# psu.net
KiCad netlist of a schematic drawn in EAGLE
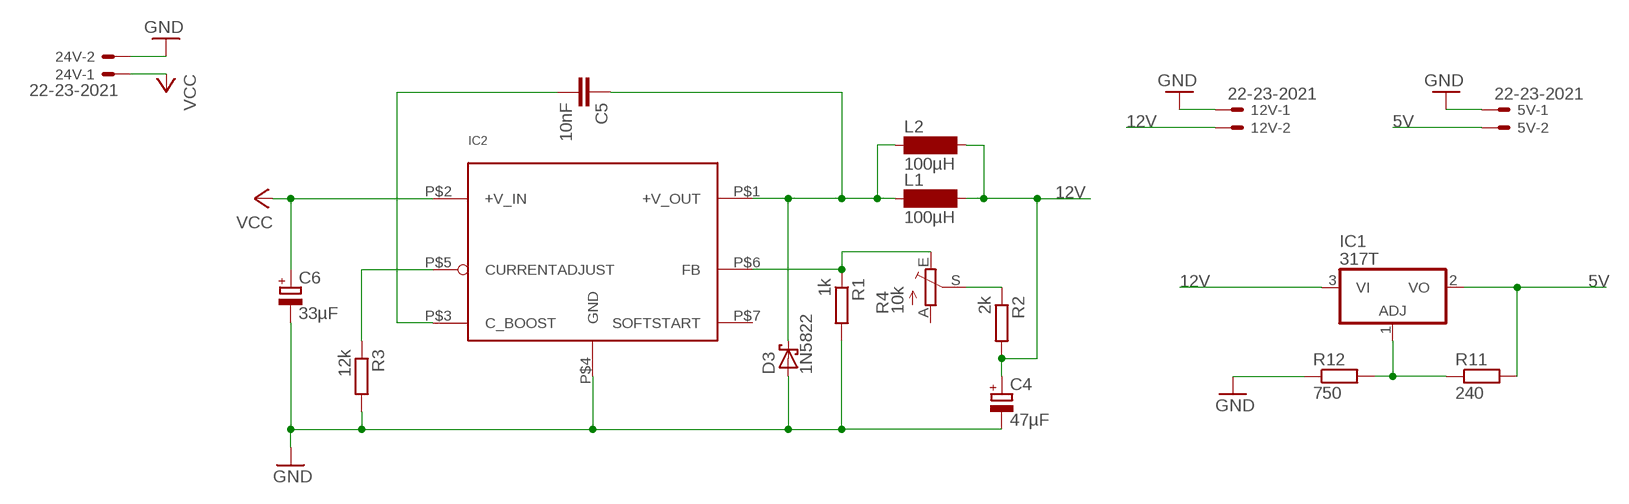
[diagram p0: schematic, sheet 1]

(export (version "E")
  (design (tool "Eeschema 10.0.6"))
  (components
    (comp (ref "5V")
      (value "22-23-2021")
      (footprint "eagle-import:22-23-2021")
      (fields (field (name "MF") "MOLEX"))
      (libsource (lib "eagle-import") (part "22-23-2021"))
    )
    (comp (ref "12V")
      (value "22-23-2021")
      (footprint "eagle-import:22-23-2021")
      (fields (field (name "MF") "MOLEX"))
      (libsource (lib "eagle-import") (part "22-23-2021"))
    )
    (comp (ref "24V")
      (value "22-23-2021")
      (footprint "eagle-import:22-23-2021")
      (fields (field (name "MF") "MOLEX"))
      (libsource (lib "eagle-import") (part "22-23-2021"))
    )
    (comp (ref "C4")
      (value "47µF")
      (footprint "eagle-import:E2,5-5")
      (libsource (lib "eagle-import") (part "CPOL-EUE2.5-5"))
    )
    (comp (ref "C5")
      (value "10nF")
      (footprint "eagle-import:C5B2.5")
      (libsource (lib "eagle-import") (part "C5/2.5"))
    )
    (comp (ref "C6")
      (value "33µF")
      (footprint "eagle-import:E2,5-5")
      (libsource (lib "eagle-import") (part "CPOL-EUE2.5-5"))
    )
    (comp (ref "D3")
      (value "1N5822")
      (footprint "eagle-import:C4111-15")
      (libsource (lib "eagle-import") (part "1N5908"))
    )
    (comp (ref "IC1")
      (value "317T")
      (footprint "eagle-import:TO220H")
      (libsource (lib "eagle-import") (part "317T"))
    )
    (comp (ref "IC2")
      (value "LM2576-T05D")
      (footprint "eagle-import:TO220-5_STAGGERED")
      (libsource (lib "eagle-import") (part "LM2576-T05D"))
    )
    (comp (ref "L1")
      (value "100µH")
      (footprint "eagle-import:SD75")
      (libsource (lib "eagle-import") (part "SD75"))
    )
    (comp (ref "L2")
      (value "100µH")
      (footprint "eagle-import:SD75")
      (libsource (lib "eagle-import") (part "SD75"))
    )
    (comp (ref "R1")
      (value "1k")
      (footprint "eagle-import:0207_10")
      (libsource (lib "eagle-import") (part "R-EU_0207/10"))
    )
    (comp (ref "R2")
      (value "2k")
      (footprint "eagle-import:0207_10")
      (libsource (lib "eagle-import") (part "R-EU_0207/10"))
    )
    (comp (ref "R3")
      (value "12k")
      (footprint "eagle-import:0207_10")
      (libsource (lib "eagle-import") (part "R-EU_0207/10"))
    )
    (comp (ref "R4")
      (value "10k")
      (footprint "eagle-import:B25P")
      (libsource (lib "eagle-import") (part "TRIM_EU-B25P"))
    )
    (comp (ref "R11")
      (value "240")
      (footprint "eagle-import:0207_10")
      (libsource (lib "eagle-import") (part "R-EU_0207/10"))
    )
    (comp (ref "R12")
      (value "750")
      (footprint "eagle-import:0207_10")
      (libsource (lib "eagle-import") (part "R-EU_0207/10"))
    )
  )
  (nets
    (net (code "1") (name "/5V") (class "Default")
      (node (ref "5V") (pin "2") (pinfunction "S_2") (pintype "passive"))
      (node (ref "IC1") (pin "2") (pinfunction "VO_2") (pintype "passive"))
      (node (ref "R11") (pin "2") (pinfunction "2_2") (pintype "passive"))
    )
    (net (code "2") (name "/12V") (class "Default")
      (node (ref "12V") (pin "2") (pinfunction "S_2") (pintype "passive"))
      (node (ref "C4") (pin "+") (pinfunction "+_+") (pintype "passive"))
      (node (ref "IC1") (pin "3") (pinfunction "VI_3") (pintype "input"))
      (node (ref "L1") (pin "2") (pinfunction "2_2") (pintype "passive"))
      (node (ref "L2") (pin "2") (pinfunction "2_2") (pintype "passive"))
      (node (ref "R2") (pin "2") (pinfunction "2_2") (pintype "passive"))
    )
    (net (code "3") (name "GND") (class "Default")
      (node (ref "12V") (pin "1") (pinfunction "S_1") (pintype "passive"))
      (node (ref "24V") (pin "2") (pinfunction "S_2") (pintype "passive"))
      (node (ref "5V") (pin "1") (pinfunction "S_1") (pintype "passive"))
      (node (ref "C4") (pin "-") (pinfunction "-_-") (pintype "passive"))
      (node (ref "C6") (pin "-") (pinfunction "-_-") (pintype "passive"))
      (node (ref "D3") (pin "A") (pinfunction "A_A") (pintype "passive"))
      (node (ref "IC2") (pin "P$4") (pinfunction "GND_P$4") (pintype "power_in"))
      (node (ref "R1") (pin "2") (pinfunction "2_2") (pintype "passive"))
      (node (ref "R12") (pin "1") (pinfunction "1_1") (pintype "passive"))
      (node (ref "R3") (pin "2") (pinfunction "2_2") (pintype "passive"))
    )
    (net (code "4") (name "Net-(IC1-ADJ)") (class "Default")
      (node (ref "IC1") (pin "1") (pinfunction "ADJ_1") (pintype "input"))
      (node (ref "R11") (pin "1") (pinfunction "1_1") (pintype "passive"))
      (node (ref "R12") (pin "2") (pinfunction "2_2") (pintype "passive"))
    )
    (net (code "5") (name "Net-(IC2-+V_OUT)") (class "Default")
      (node (ref "C5") (pin "1") (pinfunction "1_1") (pintype "passive"))
      (node (ref "D3") (pin "C") (pinfunction "C_C") (pintype "passive"))
      (node (ref "IC2") (pin "P$1") (pinfunction "+V_OUT_P$1") (pintype "output"))
      (node (ref "L1") (pin "1") (pinfunction "1_1") (pintype "passive"))
      (node (ref "L2") (pin "1") (pinfunction "1_1") (pintype "passive"))
    )
    (net (code "6") (name "Net-(IC2-CURRENTADJUST)") (class "Default")
      (node (ref "IC2") (pin "P$5") (pinfunction "CURRENTADJUST_P$5") (pintype "input"))
      (node (ref "R3") (pin "1") (pinfunction "1_1") (pintype "passive"))
    )
    (net (code "7") (name "Net-(IC2-C_BOOST)") (class "Default")
      (node (ref "C5") (pin "2") (pinfunction "2_2") (pintype "passive"))
      (node (ref "IC2") (pin "P$3") (pinfunction "C_BOOST_P$3") (pintype "input"))
    )
    (net (code "8") (name "Net-(IC2-FB)") (class "Default")
      (node (ref "IC2") (pin "P$6") (pinfunction "FB_P$6") (pintype "input"))
      (node (ref "R1") (pin "1") (pinfunction "1_1") (pintype "passive"))
      (node (ref "R4") (pin "E") (pinfunction "E_E") (pintype "passive"))
    )
    (net (code "9") (name "Net-(R2-Pad1)") (class "Default")
      (node (ref "R2") (pin "1") (pinfunction "1_1") (pintype "passive"))
      (node (ref "R4") (pin "S") (pinfunction "S_S") (pintype "passive"))
    )
    (net (code "10") (name "VCC") (class "Default")
      (node (ref "24V") (pin "1") (pinfunction "S_1") (pintype "passive"))
      (node (ref "C6") (pin "+") (pinfunction "+_+") (pintype "passive"))
      (node (ref "IC2") (pin "P$2") (pinfunction "+V_IN_P$2") (pintype "input"))
    )
    (net (code "11") (name "unconnected-(IC2-SOFTSTART-PadP$7)") (class "Default")
      (node (ref "IC2") (pin "P$7") (pinfunction "SOFTSTART_P$7") (pintype "input"))
    )
    (net (code "12") (name "unconnected-(R4-PadA)") (class "Default")
      (node (ref "R4") (pin "A") (pinfunction "A_A") (pintype "passive"))
    )
  )
)
